# ACC_charger.net
KiCad netlist of a schematic drawn in Altium Designer
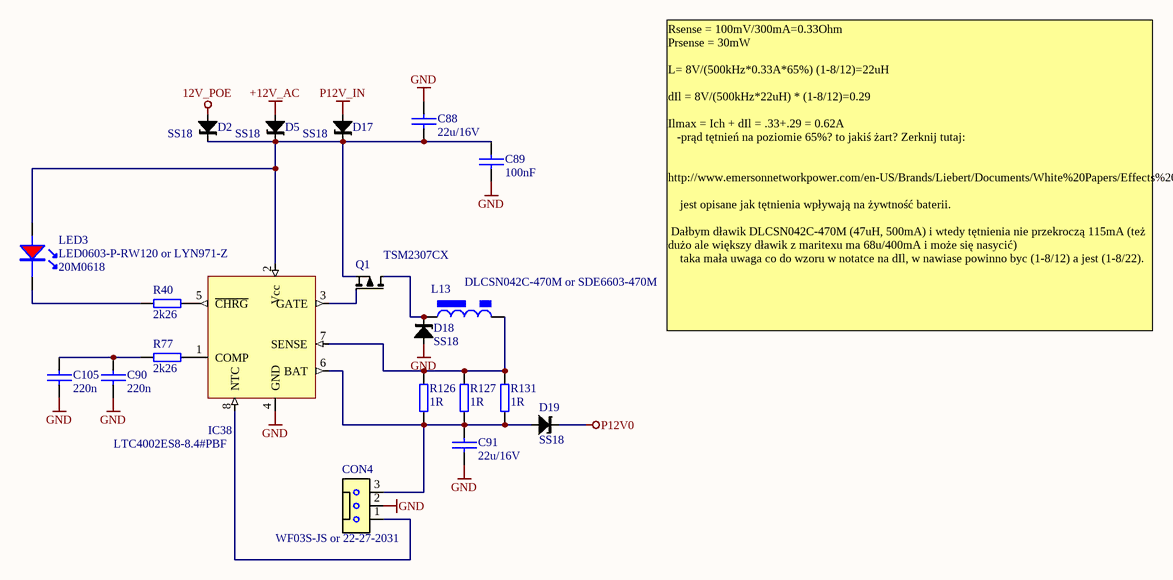
[diagram p0: ACC_charger.SchDoc]

(export (version "E")
  (design (tool "Eeschema 10.0.6"))
  (components
    (comp (ref "C88")
      (value "22u/16V")
      (footprint "1206C")
      (description "Capacitor SMD")
      (libsource (lib "LIBRARY_SCH") (part "CAP_SMD_1206"))
    )
    (comp (ref "C89")
      (value "100nF")
      (footprint "0402C")
      (description "Capacitor SMD")
      (libsource (lib "LIBRARY_SCH") (part "CAP_SMD_0402"))
    )
    (comp (ref "C90")
      (value "220n")
      (footprint "0603C")
      (description "Capacitor SMD")
      (libsource (lib "LIBRARY_SCH") (part "CAP_SMD_0603"))
    )
    (comp (ref "C91")
      (value "22u/16V")
      (footprint "1206C")
      (description "Capacitor SMD")
      (libsource (lib "LIBRARY_SCH") (part "CAP_SMD_1206"))
    )
    (comp (ref "C105")
      (value "220n")
      (footprint "0603C")
      (description "Capacitor SMD")
      (libsource (lib "LIBRARY_SCH") (part "CAP_SMD_0603"))
    )
    (comp (ref "CON4")
      (value "WF03S-JS or 22-27-2031")
      (footprint "CON_WF03S-LF")
      (description "2.54mm crimped terminal header")
      (libsource (lib "LIBRARY_SCH") (part "CON_3_2.54_key"))
    )
    (comp (ref "D2")
      (value "SS18")
      (footprint "DO-214AC/SMA")
      (description "shottky diode (Maritex)")
      (libsource (lib "LIBRARY_SCH") (part "shottky_SS14_18"))
    )
    (comp (ref "D5")
      (value "SS18")
      (footprint "DO-214AC/SMA")
      (description "shottky diode (Maritex)")
      (libsource (lib "LIBRARY_SCH") (part "shottky_SS14_18"))
    )
    (comp (ref "D17")
      (value "SS18")
      (footprint "DO-214AC/SMA")
      (description "shottky diode (Maritex)")
      (libsource (lib "LIBRARY_SCH") (part "shottky_SS14_18"))
    )
    (comp (ref "D18")
      (value "SS18")
      (footprint "DO-214AC/SMA")
      (description "shottky diode (Maritex)")
      (libsource (lib "") (part "shottky_SS14_18_2"))
    )
    (comp (ref "D19")
      (value "SS18")
      (footprint "DO-214AC/SMA")
      (description "shottky diode (Maritex)")
      (libsource (lib "") (part "shottky_SS14_18_1"))
    )
    (comp (ref "IC38")
      (value "LTC4002ES8-8.4#PBF")
      (footprint "SO-8")
      (description "Standalone Li-Ion  Switch Mode Battery Charger")
      (libsource (lib "LIBRARY_SCH") (part "PM_LTC4002ES8-8.4"))
    )
    (comp (ref "L13")
      (value "DLCSN042C-470M or SDE6603-470M")
      (footprint "L_DLCSN042C")
      (description "47uH, 0.5A, 0.64R, inductor (Maritex)")
      (libsource (lib "LIBRARY_SCH") (part "L_POWER_DLCSN042C_47uH"))
    )
    (comp (ref "LED3")
      (value "LED0603-P-RW120 or LYN971-Z")
      (footprint "led_0603R")
      (description "LED 0603 red")
      (fields (field (name "SUPPLIER PART NUMBER 2") "20M0618"))
      (libsource (lib "LIBRARY_SCH") (part "LED_0603R"))
    )
    (comp (ref "Q1")
      (value "TSM2307CX")
      (footprint "sot-23")
      (description "P MOSFET 30V, 0.14R, 2A")
      (libsource (lib "LIBRARY_SCH") (part "Q_TSM2307CX"))
    )
    (comp (ref "R40")
      (value "2k26")
      (footprint "0603R")
      (description "SMD Resistor")
      (libsource (lib "LIBRARY_SCH") (part "RES_0603"))
    )
    (comp (ref "R77")
      (value "2k26")
      (footprint "0603R")
      (description "SMD Resistor")
      (libsource (lib "LIBRARY_SCH") (part "RES_0603"))
    )
    (comp (ref "R126")
      (value "1R")
      (footprint "0603R")
      (description "SMD Resistor")
      (libsource (lib "LIBRARY_SCH") (part "RES_0603"))
    )
    (comp (ref "R127")
      (value "1R")
      (footprint "0603R")
      (description "SMD Resistor")
      (libsource (lib "LIBRARY_SCH") (part "RES_0603"))
    )
    (comp (ref "R131")
      (value "1R")
      (footprint "0603R")
      (description "SMD Resistor")
      (libsource (lib "LIBRARY_SCH") (part "RES_0603"))
    )
  )
  (nets
    (net (code "1") (name "+12V_AC") (class "Default")
      (node (ref "D5") (pin "A") (pinfunction "A_A") (pintype "passive"))
    )
    (net (code "2") (name "12V_POE") (class "Default")
      (node (ref "D2") (pin "A") (pinfunction "A_A") (pintype "passive"))
    )
    (net (code "3") (name "GND") (class "Default")
      (node (ref "C105") (pin "2") (pinfunction "2_2") (pintype "passive"))
      (node (ref "C88") (pin "1") (pinfunction "1_1") (pintype "passive"))
      (node (ref "C89") (pin "2") (pinfunction "2_2") (pintype "passive"))
      (node (ref "C90") (pin "2") (pinfunction "2_2") (pintype "passive"))
      (node (ref "C91") (pin "2") (pinfunction "2_2") (pintype "passive"))
      (node (ref "CON4") (pin "2") (pinfunction "2_2") (pintype "bidirectional"))
      (node (ref "D18") (pin "A") (pinfunction "A_A") (pintype "passive"))
      (node (ref "IC38") (pin "4") (pinfunction "GND_4") (pintype "power_in"))
    )
    (net (code "4") (name "Net-(C105-Pad1)") (class "Default")
      (node (ref "C105") (pin "1") (pinfunction "1_1") (pintype "passive"))
      (node (ref "C90") (pin "1") (pinfunction "1_1") (pintype "passive"))
      (node (ref "R77") (pin "1") (pinfunction "1_1") (pintype "passive"))
    )
    (net (code "5") (name "Net-(IC38-BAT)") (class "Default")
      (node (ref "C91") (pin "1") (pinfunction "1_1") (pintype "passive"))
      (node (ref "CON4") (pin "3") (pinfunction "3_3") (pintype "bidirectional"))
      (node (ref "D19") (pin "A") (pinfunction "A_A") (pintype "passive"))
      (node (ref "IC38") (pin "6") (pinfunction "BAT_6") (pintype "output"))
      (node (ref "R126") (pin "1") (pinfunction "1_1") (pintype "passive"))
      (node (ref "R127") (pin "1") (pinfunction "1_1") (pintype "passive"))
      (node (ref "R131") (pin "1") (pinfunction "1_1") (pintype "passive"))
    )
    (net (code "6") (name "Net-(IC38-COMP)") (class "Default")
      (node (ref "IC38") (pin "1") (pinfunction "COMP_1") (pintype "passive"))
      (node (ref "R77") (pin "2") (pinfunction "2_2") (pintype "passive"))
    )
    (net (code "7") (name "Net-(IC38-GATE)") (class "Default")
      (node (ref "IC38") (pin "3") (pinfunction "GATE_3") (pintype "output"))
      (node (ref "Q1") (pin "1") (pinfunction "G_1") (pintype "input"))
    )
    (net (code "8") (name "Net-(IC38-NTC)") (class "Default")
      (node (ref "CON4") (pin "1") (pinfunction "1_1") (pintype "bidirectional"))
      (node (ref "IC38") (pin "8") (pinfunction "NTC_8") (pintype "input"))
    )
    (net (code "9") (name "Net-(IC38-SENSE)") (class "Default")
      (node (ref "IC38") (pin "7") (pinfunction "SENSE_7") (pintype "input"))
      (node (ref "L13") (pin "2") (pintype "passive"))
      (node (ref "R126") (pin "2") (pinfunction "2_2") (pintype "passive"))
      (node (ref "R127") (pin "2") (pinfunction "2_2") (pintype "passive"))
      (node (ref "R131") (pin "2") (pinfunction "2_2") (pintype "passive"))
    )
    (net (code "10") (name "Net-(IC38-Vcc)") (class "Default")
      (node (ref "C88") (pin "2") (pinfunction "2_2") (pintype "passive"))
      (node (ref "C89") (pin "1") (pinfunction "1_1") (pintype "passive"))
      (node (ref "D17") (pin "K") (pinfunction "K_K") (pintype "passive"))
      (node (ref "D2") (pin "K") (pinfunction "K_K") (pintype "passive"))
      (node (ref "D5") (pin "K") (pinfunction "K_K") (pintype "passive"))
      (node (ref "IC38") (pin "2") (pinfunction "Vcc_2") (pintype "input"))
      (node (ref "LED3") (pin "A") (pinfunction "A_A") (pintype "passive"))
      (node (ref "Q1") (pin "2") (pinfunction "S_2") (pintype "passive"))
    )
    (net (code "11") (name "Net-(IC38-~{CHRG})") (class "Default")
      (node (ref "IC38") (pin "5") (pinfunction "~{CHRG}_5") (pintype "output"))
      (node (ref "R40") (pin "2") (pinfunction "2_2") (pintype "passive"))
    )
    (net (code "12") (name "Net-(LED3-PadK)") (class "Default")
      (node (ref "LED3") (pin "K") (pinfunction "K_K") (pintype "passive"))
      (node (ref "R40") (pin "1") (pinfunction "1_1") (pintype "passive"))
    )
    (net (code "13") (name "Net-(Q1-D)") (class "Default")
      (node (ref "D18") (pin "K") (pinfunction "K_K") (pintype "passive"))
      (node (ref "L13") (pin "1") (pintype "passive"))
      (node (ref "Q1") (pin "3") (pinfunction "D_3") (pintype "passive"))
    )
    (net (code "14") (name "P12V0") (class "Default")
      (node (ref "D19") (pin "K") (pinfunction "K_K") (pintype "passive"))
    )
    (net (code "15") (name "P12V_IN") (class "Default")
      (node (ref "D17") (pin "A") (pinfunction "A_A") (pintype "passive"))
    )
  )
)
